# 4channelWormbotShield_fixed_PCBv03_addSS.net
KiCad netlist of a schematic drawn in EAGLE
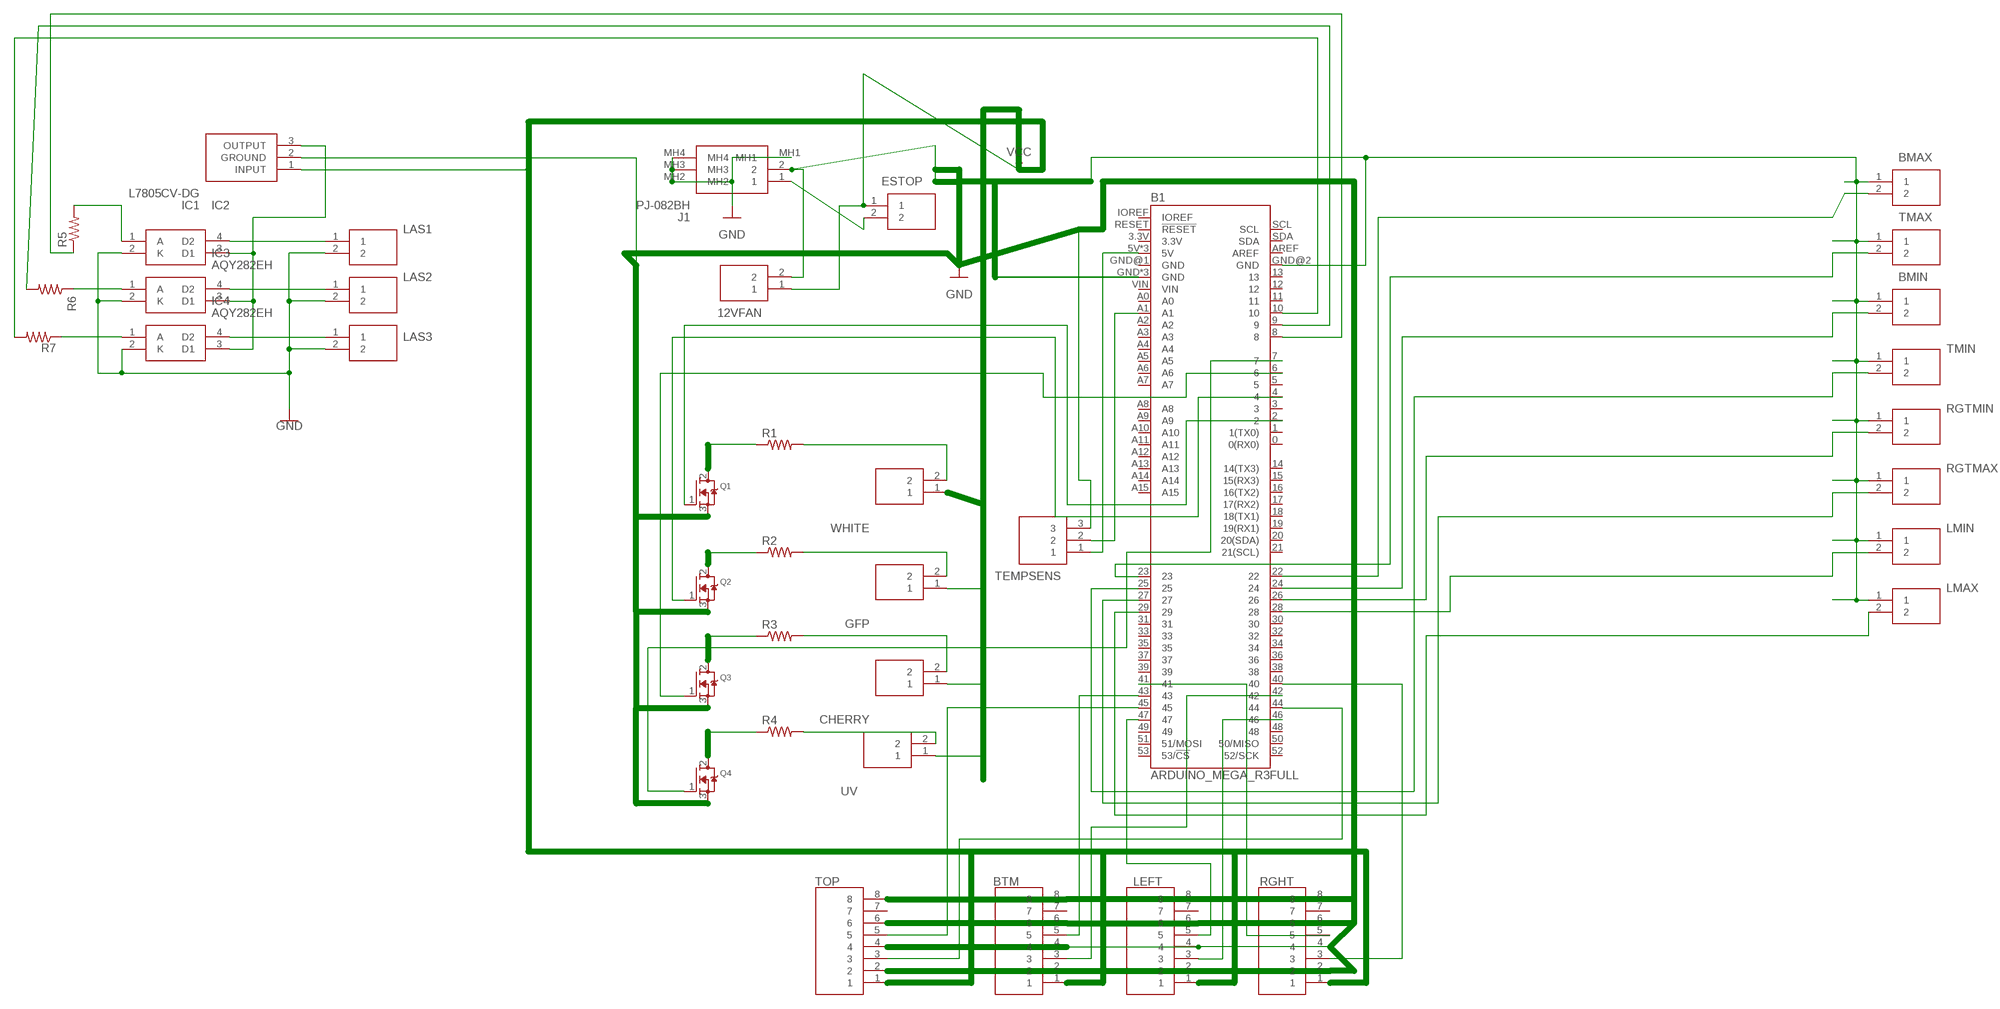
[diagram p0: schematic, sheet 1]

(export (version "E")
  (design (tool "Eeschema 10.0.6"))
  (components
    (comp (ref "12VFAN")
      (value "1725656")
      (footprint "eagle-import:1725656")
      (fields (field (name "MOUSER_PART_NUMBER") "651-1725656"))
      (libsource (lib "eagle-import") (part "1725656"))
    )
    (comp (ref "B1")
      (value "ARDUINO_MEGA_R3FULL")
      (footprint "eagle-import:ARDUINO_MEGA_NO_SILK")
      (libsource (lib "eagle-import") (part "ARDUINO_MEGA_R3FULL"))
    )
    (comp (ref "BMAX")
      (value "1725656")
      (footprint "eagle-import:1725656")
      (fields (field (name "MOUSER_PART_NUMBER") "651-1725656"))
      (libsource (lib "eagle-import") (part "1725656"))
    )
    (comp (ref "BMIN")
      (value "1725656")
      (footprint "eagle-import:1725656")
      (fields (field (name "MOUSER_PART_NUMBER") "651-1725656"))
      (libsource (lib "eagle-import") (part "1725656"))
    )
    (comp (ref "BTM")
      (value "1725711")
      (footprint "eagle-import:1725711")
      (fields (field (name "MOUSER_PART_NUMBER") "651-1725711"))
      (libsource (lib "eagle-import") (part "1725711"))
    )
    (comp (ref "CHERRY")
      (value "1725656")
      (footprint "eagle-import:1725656")
      (fields (field (name "MOUSER_PART_NUMBER") "651-1725656"))
      (libsource (lib "eagle-import") (part "1725656"))
    )
    (comp (ref "ESTOP")
      (value "TB003-500-P02BE")
      (footprint "eagle-import:SHDR2W100P0X500_1X2_1000X780X1")
      (fields (field (name "MOUSER_PART_NUMBER") "490-TB003-500-P02BE"))
      (libsource (lib "eagle-import") (part "TB003-500-P02BE"))
    )
    (comp (ref "GFP")
      (value "1725656")
      (footprint "eagle-import:1725656")
      (fields (field (name "MOUSER_PART_NUMBER") "651-1725656"))
      (libsource (lib "eagle-import") (part "1725656"))
    )
    (comp (ref "IC1")
      (value "L7805CV-DG")
      (footprint "eagle-import:TO255P460X1020X2008-3P")
      (fields (field (name "MOUSER_PART_NUMBER") "511-L7805CV-DG"))
      (libsource (lib "eagle-import") (part "L7805CV-DG"))
    )
    (comp (ref "IC2")
      (value "AQY282EH")
      (footprint "eagle-import:DIP762W57P254L478H340Q4N")
      (fields (field (name "MOUSER_PART_NUMBER") "769-AQY282EH"))
      (libsource (lib "eagle-import") (part "AQY282EH"))
    )
    (comp (ref "IC3")
      (value "AQY282EH")
      (footprint "eagle-import:DIP762W57P254L478H340Q4N")
      (fields (field (name "MOUSER_PART_NUMBER") "769-AQY282EH"))
      (libsource (lib "eagle-import") (part "AQY282EH"))
    )
    (comp (ref "IC4")
      (value "AQY282EH")
      (footprint "eagle-import:DIP762W57P254L478H340Q4N")
      (fields (field (name "MOUSER_PART_NUMBER") "769-AQY282EH"))
      (libsource (lib "eagle-import") (part "AQY282EH"))
    )
    (comp (ref "J1")
      (value "PJ-082BH")
      (footprint "eagle-import:PJ082BH")
      (fields (field (name "MOUSER_PART_NUMBER") "490-PJ-082BH"))
      (libsource (lib "eagle-import") (part "PJ-082BH"))
    )
    (comp (ref "LAS1")
      (value "1725656")
      (footprint "eagle-import:1725656")
      (fields (field (name "MOUSER_PART_NUMBER") "651-1725656"))
      (libsource (lib "eagle-import") (part "1725656"))
    )
    (comp (ref "LAS2")
      (value "1725656")
      (footprint "eagle-import:1725656")
      (fields (field (name "MOUSER_PART_NUMBER") "651-1725656"))
      (libsource (lib "eagle-import") (part "1725656"))
    )
    (comp (ref "LAS3")
      (value "1725656")
      (footprint "eagle-import:1725656")
      (fields (field (name "MOUSER_PART_NUMBER") "651-1725656"))
      (libsource (lib "eagle-import") (part "1725656"))
    )
    (comp (ref "LEFT")
      (value "1725711")
      (footprint "eagle-import:1725711")
      (fields (field (name "MOUSER_PART_NUMBER") "651-1725711"))
      (libsource (lib "eagle-import") (part "1725711"))
    )
    (comp (ref "LMAX")
      (value "1725656")
      (footprint "eagle-import:1725656")
      (fields (field (name "MOUSER_PART_NUMBER") "651-1725656"))
      (libsource (lib "eagle-import") (part "1725656"))
    )
    (comp (ref "LMIN")
      (value "1725656")
      (footprint "eagle-import:1725656")
      (fields (field (name "MOUSER_PART_NUMBER") "651-1725656"))
      (libsource (lib "eagle-import") (part "1725656"))
    )
    (comp (ref "Q1")
      (value "MOSFET-NGDS_TO220V")
      (footprint "eagle-import:TO220V")
      (libsource (lib "eagle-import") (part "MOSFET-NGDS_TO220V"))
    )
    (comp (ref "Q2")
      (value "MOSFET-NGDS_TO220V")
      (footprint "eagle-import:TO220V")
      (libsource (lib "eagle-import") (part "MOSFET-NGDS_TO220V"))
    )
    (comp (ref "Q3")
      (value "MOSFET-NGDS_TO220V")
      (footprint "eagle-import:TO220V")
      (libsource (lib "eagle-import") (part "MOSFET-NGDS_TO220V"))
    )
    (comp (ref "Q4")
      (value "MOSFET-NGDS_TO220V")
      (footprint "eagle-import:TO220V")
      (libsource (lib "eagle-import") (part "MOSFET-NGDS_TO220V"))
    )
    (comp (ref "R1")
      (value "R-US_0207/10")
      (footprint "eagle-import:0207_10")
      (libsource (lib "eagle-import") (part "R-US_0207/10"))
    )
    (comp (ref "R2")
      (value "R-US_0207/10")
      (footprint "eagle-import:0207_10")
      (libsource (lib "eagle-import") (part "R-US_0207/10"))
    )
    (comp (ref "R3")
      (value "R-US_0207/10")
      (footprint "eagle-import:0207_10")
      (libsource (lib "eagle-import") (part "R-US_0207/10"))
    )
    (comp (ref "R4")
      (value "R-US_0207/10")
      (footprint "eagle-import:0207_10")
      (libsource (lib "eagle-import") (part "R-US_0207/10"))
    )
    (comp (ref "R5")
      (value "R-US_0207/10")
      (footprint "eagle-import:0207_10")
      (libsource (lib "eagle-import") (part "R-US_0207/10"))
    )
    (comp (ref "R6")
      (value "R-US_0207/10")
      (footprint "eagle-import:0207_10")
      (libsource (lib "eagle-import") (part "R-US_0207/10"))
    )
    (comp (ref "R7")
      (value "R-US_0207/10")
      (footprint "eagle-import:0207_10")
      (libsource (lib "eagle-import") (part "R-US_0207/10"))
    )
    (comp (ref "RGHT")
      (value "1725711")
      (footprint "eagle-import:1725711")
      (fields (field (name "MOUSER_PART_NUMBER") "651-1725711"))
      (libsource (lib "eagle-import") (part "1725711"))
    )
    (comp (ref "RGTMAX")
      (value "1725656")
      (footprint "eagle-import:1725656")
      (fields (field (name "MOUSER_PART_NUMBER") "651-1725656"))
      (libsource (lib "eagle-import") (part "1725656"))
    )
    (comp (ref "RGTMIN")
      (value "1725656")
      (footprint "eagle-import:1725656")
      (fields (field (name "MOUSER_PART_NUMBER") "651-1725656"))
      (libsource (lib "eagle-import") (part "1725656"))
    )
    (comp (ref "TEMPSENS")
      (value "1725669")
      (footprint "eagle-import:1725669")
      (fields (field (name "MOUSER_PART_NUMBER") "651-1725669"))
      (libsource (lib "eagle-import") (part "1725669"))
    )
    (comp (ref "TMAX")
      (value "1725656")
      (footprint "eagle-import:1725656")
      (fields (field (name "MOUSER_PART_NUMBER") "651-1725656"))
      (libsource (lib "eagle-import") (part "1725656"))
    )
    (comp (ref "TMIN")
      (value "1725656")
      (footprint "eagle-import:1725656")
      (fields (field (name "MOUSER_PART_NUMBER") "651-1725656"))
      (libsource (lib "eagle-import") (part "1725656"))
    )
    (comp (ref "TOP")
      (value "1725711")
      (footprint "eagle-import:1725711")
      (fields (field (name "MOUSER_PART_NUMBER") "651-1725711"))
      (libsource (lib "eagle-import") (part "1725711"))
    )
    (comp (ref "UV")
      (value "1725656")
      (footprint "eagle-import:1725656")
      (fields (field (name "MOUSER_PART_NUMBER") "651-1725656"))
      (libsource (lib "eagle-import") (part "1725656"))
    )
    (comp (ref "WHITE")
      (value "1725656")
      (footprint "eagle-import:1725656")
      (fields (field (name "MOUSER_PART_NUMBER") "651-1725656"))
      (libsource (lib "eagle-import") (part "1725656"))
    )
  )
  (nets
    (net (code "1") (name "GND") (class "Default")
      (node (ref "12VFAN") (pin "2") (pinfunction "2_2") (pintype "bidirectional"))
      (node (ref "B1") (pin "GND") (pinfunction "GND_GND") (pintype "bidirectional"))
      (node (ref "B1") (pin "GND@2") (pinfunction "GND_GND@2") (pintype "bidirectional"))
      (node (ref "B1") (pin "GND@3") (pinfunction "GND_GND@3") (pintype "bidirectional"))
      (node (ref "B1") (pin "GND@4") (pinfunction "GND_GND@4") (pintype "bidirectional"))
      (node (ref "BMAX") (pin "1") (pinfunction "1_1") (pintype "bidirectional"))
      (node (ref "BMIN") (pin "1") (pinfunction "1_1") (pintype "bidirectional"))
      (node (ref "BTM") (pin "2") (pinfunction "2_2") (pintype "bidirectional"))
      (node (ref "BTM") (pin "4") (pinfunction "4_4") (pintype "bidirectional"))
      (node (ref "BTM") (pin "6") (pinfunction "6_6") (pintype "bidirectional"))
      (node (ref "BTM") (pin "8") (pinfunction "8_8") (pintype "bidirectional"))
      (node (ref "IC1") (pin "2") (pinfunction "GROUND_2") (pintype "bidirectional"))
      (node (ref "IC2") (pin "2") (pinfunction "K_2") (pintype "bidirectional"))
      (node (ref "IC3") (pin "2") (pinfunction "K_2") (pintype "bidirectional"))
      (node (ref "IC4") (pin "2") (pinfunction "K_2") (pintype "bidirectional"))
      (node (ref "J1") (pin "2") (pinfunction "2_2") (pintype "bidirectional"))
      (node (ref "J1") (pin "MH1") (pinfunction "MH1_MH1") (pintype "bidirectional"))
      (node (ref "J1") (pin "MH2") (pinfunction "MH2_MH2") (pintype "bidirectional"))
      (node (ref "J1") (pin "MH3") (pinfunction "MH3_MH3") (pintype "bidirectional"))
      (node (ref "J1") (pin "MH4") (pinfunction "MH4_MH4") (pintype "bidirectional"))
      (node (ref "LAS1") (pin "2") (pinfunction "2_2") (pintype "bidirectional"))
      (node (ref "LAS2") (pin "2") (pinfunction "2_2") (pintype "bidirectional"))
      (node (ref "LAS3") (pin "2") (pinfunction "2_2") (pintype "bidirectional"))
      (node (ref "LEFT") (pin "2") (pinfunction "2_2") (pintype "bidirectional"))
      (node (ref "LEFT") (pin "4") (pinfunction "4_4") (pintype "bidirectional"))
      (node (ref "LEFT") (pin "6") (pinfunction "6_6") (pintype "bidirectional"))
      (node (ref "LEFT") (pin "8") (pinfunction "8_8") (pintype "bidirectional"))
      (node (ref "LMAX") (pin "1") (pinfunction "1_1") (pintype "bidirectional"))
      (node (ref "LMIN") (pin "1") (pinfunction "1_1") (pintype "bidirectional"))
      (node (ref "Q1") (pin "3") (pinfunction "S_3") (pintype "bidirectional"))
      (node (ref "Q2") (pin "3") (pinfunction "S_3") (pintype "bidirectional"))
      (node (ref "Q3") (pin "3") (pinfunction "S_3") (pintype "bidirectional"))
      (node (ref "Q4") (pin "3") (pinfunction "S_3") (pintype "bidirectional"))
      (node (ref "RGHT") (pin "2") (pinfunction "2_2") (pintype "bidirectional"))
      (node (ref "RGHT") (pin "4") (pinfunction "4_4") (pintype "bidirectional"))
      (node (ref "RGHT") (pin "6") (pinfunction "6_6") (pintype "bidirectional"))
      (node (ref "RGHT") (pin "8") (pinfunction "8_8") (pintype "bidirectional"))
      (node (ref "RGTMAX") (pin "1") (pinfunction "1_1") (pintype "bidirectional"))
      (node (ref "RGTMIN") (pin "1") (pinfunction "1_1") (pintype "bidirectional"))
      (node (ref "TEMPSENS") (pin "3") (pinfunction "3_3") (pintype "bidirectional"))
      (node (ref "TMAX") (pin "1") (pinfunction "1_1") (pintype "bidirectional"))
      (node (ref "TMIN") (pin "1") (pinfunction "1_1") (pintype "bidirectional"))
      (node (ref "TOP") (pin "2") (pinfunction "2_2") (pintype "bidirectional"))
      (node (ref "TOP") (pin "4") (pinfunction "4_4") (pintype "bidirectional"))
      (node (ref "TOP") (pin "6") (pinfunction "6_6") (pintype "bidirectional"))
      (node (ref "TOP") (pin "8") (pinfunction "8_8") (pintype "bidirectional"))
    )
    (net (code "2") (name "Net-(B1-5V-Pad5V@1)") (class "Default")
      (node (ref "B1") (pin "5V") (pinfunction "5V_5V") (pintype "bidirectional"))
      (node (ref "B1") (pin "5V@1") (pinfunction "5V_5V@1") (pintype "bidirectional"))
      (node (ref "B1") (pin "5V@2") (pinfunction "5V_5V@2") (pintype "bidirectional"))
      (node (ref "TEMPSENS") (pin "1") (pinfunction "1_1") (pintype "bidirectional"))
    )
    (net (code "3") (name "Net-(B1-Pad8)") (class "Default")
      (node (ref "B1") (pin "8") (pinfunction "8_8") (pintype "bidirectional"))
      (node (ref "R5") (pin "1") (pinfunction "1_1") (pintype "passive"))
    )
    (net (code "4") (name "Net-(B1-Pad9)") (class "Default")
      (node (ref "B1") (pin "9") (pinfunction "9_9") (pintype "bidirectional"))
      (node (ref "R6") (pin "2") (pinfunction "2_2") (pintype "passive"))
    )
    (net (code "5") (name "Net-(B1-Pad10)") (class "Default")
      (node (ref "B1") (pin "10") (pinfunction "10_10") (pintype "bidirectional"))
      (node (ref "R7") (pin "2") (pinfunction "2_2") (pintype "passive"))
    )
    (net (code "6") (name "Net-(B1-Pad22)") (class "Default")
      (node (ref "B1") (pin "22") (pinfunction "22_22") (pintype "bidirectional"))
      (node (ref "BMAX") (pin "2") (pinfunction "2_2") (pintype "bidirectional"))
    )
    (net (code "7") (name "Net-(B1-Pad23)") (class "Default")
      (node (ref "B1") (pin "23") (pinfunction "23_23") (pintype "bidirectional"))
      (node (ref "TMAX") (pin "2") (pinfunction "2_2") (pintype "bidirectional"))
    )
    (net (code "8") (name "Net-(B1-Pad24)") (class "Default")
      (node (ref "B1") (pin "24") (pinfunction "24_24") (pintype "bidirectional"))
      (node (ref "BMIN") (pin "2") (pinfunction "2_2") (pintype "bidirectional"))
    )
    (net (code "9") (name "Net-(B1-Pad25)") (class "Default")
      (node (ref "B1") (pin "25") (pinfunction "25_25") (pintype "bidirectional"))
      (node (ref "TMIN") (pin "2") (pinfunction "2_2") (pintype "bidirectional"))
    )
    (net (code "10") (name "Net-(B1-Pad26)") (class "Default")
      (node (ref "B1") (pin "26") (pinfunction "26_26") (pintype "bidirectional"))
      (node (ref "RGTMIN") (pin "2") (pinfunction "2_2") (pintype "bidirectional"))
    )
    (net (code "11") (name "Net-(B1-Pad27)") (class "Default")
      (node (ref "B1") (pin "27") (pinfunction "27_27") (pintype "bidirectional"))
      (node (ref "RGTMAX") (pin "2") (pinfunction "2_2") (pintype "bidirectional"))
    )
    (net (code "12") (name "Net-(B1-Pad28)") (class "Default")
      (node (ref "B1") (pin "28") (pinfunction "28_28") (pintype "bidirectional"))
      (node (ref "LMIN") (pin "2") (pinfunction "2_2") (pintype "bidirectional"))
    )
    (net (code "13") (name "Net-(B1-Pad29)") (class "Default")
      (node (ref "B1") (pin "29") (pinfunction "29_29") (pintype "bidirectional"))
      (node (ref "LMAX") (pin "2") (pinfunction "2_2") (pintype "bidirectional"))
    )
    (net (code "14") (name "Net-(B1-Pad40)") (class "Default")
      (node (ref "B1") (pin "40") (pinfunction "40_40") (pintype "bidirectional"))
      (node (ref "RGHT") (pin "3") (pinfunction "3_3") (pintype "bidirectional"))
    )
    (net (code "15") (name "Net-(B1-Pad41)") (class "Default")
      (node (ref "B1") (pin "41") (pinfunction "41_41") (pintype "bidirectional"))
      (node (ref "RGHT") (pin "5") (pinfunction "5_5") (pintype "bidirectional"))
    )
    (net (code "16") (name "Net-(B1-Pad42)") (class "Default")
      (node (ref "B1") (pin "42") (pinfunction "42_42") (pintype "bidirectional"))
      (node (ref "BTM") (pin "3") (pinfunction "3_3") (pintype "bidirectional"))
    )
    (net (code "17") (name "Net-(B1-Pad43)") (class "Default")
      (node (ref "B1") (pin "43") (pinfunction "43_43") (pintype "bidirectional"))
      (node (ref "BTM") (pin "5") (pinfunction "5_5") (pintype "bidirectional"))
    )
    (net (code "18") (name "Net-(B1-Pad44)") (class "Default")
      (node (ref "B1") (pin "44") (pinfunction "44_44") (pintype "bidirectional"))
      (node (ref "TOP") (pin "3") (pinfunction "3_3") (pintype "bidirectional"))
    )
    (net (code "19") (name "Net-(B1-Pad45)") (class "Default")
      (node (ref "B1") (pin "45") (pinfunction "45_45") (pintype "bidirectional"))
      (node (ref "TOP") (pin "5") (pinfunction "5_5") (pintype "bidirectional"))
    )
    (net (code "20") (name "Net-(B1-Pad46)") (class "Default")
      (node (ref "B1") (pin "46") (pinfunction "46_46") (pintype "bidirectional"))
      (node (ref "LEFT") (pin "3") (pinfunction "3_3") (pintype "bidirectional"))
    )
    (net (code "21") (name "Net-(B1-Pad47)") (class "Default")
      (node (ref "B1") (pin "47") (pinfunction "47_47") (pintype "bidirectional"))
      (node (ref "LEFT") (pin "5") (pinfunction "5_5") (pintype "bidirectional"))
    )
    (net (code "22") (name "Net-(B1-PadA1)") (class "Default")
      (node (ref "B1") (pin "A1") (pinfunction "A1_A1") (pintype "bidirectional"))
      (node (ref "TEMPSENS") (pin "2") (pinfunction "2_2") (pintype "bidirectional"))
    )
    (net (code "23") (name "Net-(CHERRY-Pad2)") (class "Default")
      (node (ref "CHERRY") (pin "2") (pinfunction "2_2") (pintype "bidirectional"))
      (node (ref "R3") (pin "2") (pinfunction "2_2") (pintype "passive"))
    )
    (net (code "24") (name "Net-(ESTOP-Pad2)") (class "Default")
      (node (ref "ESTOP") (pin "2") (pinfunction "2_2") (pintype "bidirectional"))
      (node (ref "J1") (pin "1") (pinfunction "1_1") (pintype "bidirectional"))
    )
    (net (code "25") (name "Net-(GFP-Pad2)") (class "Default")
      (node (ref "GFP") (pin "2") (pinfunction "2_2") (pintype "bidirectional"))
      (node (ref "R2") (pin "2") (pinfunction "2_2") (pintype "passive"))
    )
    (net (code "26") (name "Net-(IC1-OUTPUT)") (class "Default")
      (node (ref "IC1") (pin "3") (pinfunction "OUTPUT_3") (pintype "bidirectional"))
      (node (ref "IC2") (pin "3") (pinfunction "D1_3") (pintype "bidirectional"))
      (node (ref "IC3") (pin "3") (pinfunction "D1_3") (pintype "bidirectional"))
      (node (ref "IC4") (pin "3") (pinfunction "D1_3") (pintype "bidirectional"))
    )
    (net (code "27") (name "Net-(IC2-A)") (class "Default")
      (node (ref "IC2") (pin "1") (pinfunction "A_1") (pintype "bidirectional"))
      (node (ref "R5") (pin "2") (pinfunction "2_2") (pintype "passive"))
    )
    (net (code "28") (name "Net-(IC2-D2)") (class "Default")
      (node (ref "IC2") (pin "4") (pinfunction "D2_4") (pintype "bidirectional"))
      (node (ref "LAS1") (pin "1") (pinfunction "1_1") (pintype "bidirectional"))
    )
    (net (code "29") (name "Net-(IC3-A)") (class "Default")
      (node (ref "IC3") (pin "1") (pinfunction "A_1") (pintype "bidirectional"))
      (node (ref "R6") (pin "1") (pinfunction "1_1") (pintype "passive"))
    )
    (net (code "30") (name "Net-(IC3-D2)") (class "Default")
      (node (ref "IC3") (pin "4") (pinfunction "D2_4") (pintype "bidirectional"))
      (node (ref "LAS2") (pin "1") (pinfunction "1_1") (pintype "bidirectional"))
    )
    (net (code "31") (name "Net-(IC4-A)") (class "Default")
      (node (ref "IC4") (pin "1") (pinfunction "A_1") (pintype "bidirectional"))
      (node (ref "R7") (pin "1") (pinfunction "1_1") (pintype "passive"))
    )
    (net (code "32") (name "Net-(IC4-D2)") (class "Default")
      (node (ref "IC4") (pin "4") (pinfunction "D2_4") (pintype "bidirectional"))
      (node (ref "LAS3") (pin "1") (pinfunction "1_1") (pintype "bidirectional"))
    )
    (net (code "33") (name "Net-(Q1-D)") (class "Default")
      (node (ref "Q1") (pin "2") (pinfunction "D_2") (pintype "bidirectional"))
      (node (ref "R1") (pin "1") (pinfunction "1_1") (pintype "passive"))
    )
    (net (code "34") (name "Net-(Q1-G)") (class "Default")
      (node (ref "B1") (pin "2") (pinfunction "2_2") (pintype "bidirectional"))
      (node (ref "Q1") (pin "1") (pinfunction "G_1") (pintype "bidirectional"))
    )
    (net (code "35") (name "Net-(Q2-D)") (class "Default")
      (node (ref "Q2") (pin "2") (pinfunction "D_2") (pintype "bidirectional"))
      (node (ref "R2") (pin "1") (pinfunction "1_1") (pintype "passive"))
    )
    (net (code "36") (name "Net-(Q2-G)") (class "Default")
      (node (ref "B1") (pin "4") (pinfunction "4_4") (pintype "bidirectional"))
      (node (ref "Q2") (pin "1") (pinfunction "G_1") (pintype "bidirectional"))
    )
    (net (code "37") (name "Net-(Q3-D)") (class "Default")
      (node (ref "Q3") (pin "2") (pinfunction "D_2") (pintype "bidirectional"))
      (node (ref "R3") (pin "1") (pinfunction "1_1") (pintype "passive"))
    )
    (net (code "38") (name "Net-(Q3-G)") (class "Default")
      (node (ref "B1") (pin "6") (pinfunction "6_6") (pintype "bidirectional"))
      (node (ref "Q3") (pin "1") (pinfunction "G_1") (pintype "bidirectional"))
    )
    (net (code "39") (name "Net-(Q4-D)") (class "Default")
      (node (ref "Q4") (pin "2") (pinfunction "D_2") (pintype "bidirectional"))
      (node (ref "R4") (pin "1") (pinfunction "1_1") (pintype "passive"))
    )
    (net (code "40") (name "Net-(Q4-G)") (class "Default")
      (node (ref "B1") (pin "7") (pinfunction "7_7") (pintype "bidirectional"))
      (node (ref "Q4") (pin "1") (pinfunction "G_1") (pintype "bidirectional"))
    )
    (net (code "41") (name "Net-(R1-Pad2)") (class "Default")
      (node (ref "R1") (pin "2") (pinfunction "2_2") (pintype "passive"))
      (node (ref "WHITE") (pin "2") (pinfunction "2_2") (pintype "bidirectional"))
    )
    (net (code "42") (name "Net-(R4-Pad2)") (class "Default")
      (node (ref "R4") (pin "2") (pinfunction "2_2") (pintype "passive"))
      (node (ref "UV") (pin "2") (pinfunction "2_2") (pintype "bidirectional"))
    )
    (net (code "43") (name "VCC") (class "Default")
      (node (ref "12VFAN") (pin "1") (pinfunction "1_1") (pintype "bidirectional"))
      (node (ref "BTM") (pin "1") (pinfunction "1_1") (pintype "bidirectional"))
      (node (ref "CHERRY") (pin "1") (pinfunction "1_1") (pintype "bidirectional"))
      (node (ref "ESTOP") (pin "1") (pinfunction "1_1") (pintype "bidirectional"))
      (node (ref "GFP") (pin "1") (pinfunction "1_1") (pintype "bidirectional"))
      (node (ref "IC1") (pin "1") (pinfunction "INPUT_1") (pintype "bidirectional"))
      (node (ref "LEFT") (pin "1") (pinfunction "1_1") (pintype "bidirectional"))
      (node (ref "RGHT") (pin "1") (pinfunction "1_1") (pintype "bidirectional"))
      (node (ref "TOP") (pin "1") (pinfunction "1_1") (pintype "bidirectional"))
      (node (ref "UV") (pin "1") (pinfunction "1_1") (pintype "bidirectional"))
      (node (ref "WHITE") (pin "1") (pinfunction "1_1") (pintype "bidirectional"))
    )
    (net (code "44") (name "unconnected-(B1-0(RX0)-Pad0)") (class "Default")
      (node (ref "B1") (pin "0") (pinfunction "0(RX0)_0") (pintype "bidirectional"))
    )
    (net (code "45") (name "unconnected-(B1-1(TX0)-Pad1)") (class "Default")
      (node (ref "B1") (pin "1") (pinfunction "1(TX0)_1") (pintype "bidirectional"))
    )
    (net (code "46") (name "unconnected-(B1-14(TX3)-Pad14)") (class "Default")
      (node (ref "B1") (pin "14") (pinfunction "14(TX3)_14") (pintype "bidirectional"))
    )
    (net (code "47") (name "unconnected-(B1-15(RX3)-Pad15)") (class "Default")
      (node (ref "B1") (pin "15") (pinfunction "15(RX3)_15") (pintype "bidirectional"))
    )
    (net (code "48") (name "unconnected-(B1-16(TX2)-Pad16)") (class "Default")
      (node (ref "B1") (pin "16") (pinfunction "16(TX2)_16") (pintype "bidirectional"))
    )
    (net (code "49") (name "unconnected-(B1-17(RX2)-Pad17)") (class "Default")
      (node (ref "B1") (pin "17") (pinfunction "17(RX2)_17") (pintype "bidirectional"))
    )
    (net (code "50") (name "unconnected-(B1-18(TX1)-Pad18)") (class "Default")
      (node (ref "B1") (pin "18") (pinfunction "18(TX1)_18") (pintype "bidirectional"))
    )
    (net (code "51") (name "unconnected-(B1-19(RX1)-Pad19)") (class "Default")
      (node (ref "B1") (pin "19") (pinfunction "19(RX1)_19") (pintype "bidirectional"))
    )
    (net (code "52") (name "unconnected-(B1-20(SDA)-Pad20)") (class "Default")
      (node (ref "B1") (pin "20") (pinfunction "20(SDA)_20") (pintype "bidirectional"))
    )
    (net (code "53") (name "unconnected-(B1-21(SCL)-Pad21)") (class "Default")
      (node (ref "B1") (pin "21") (pinfunction "21(SCL)_21") (pintype "bidirectional"))
    )
    (net (code "54") (name "unconnected-(B1-50{slash}MISO-Pad50)") (class "Default")
      (node (ref "B1") (pin "50") (pinfunction "50/MISO_50") (pintype "bidirectional"))
    )
    (net (code "55") (name "unconnected-(B1-51{slash}MOSI-Pad51)") (class "Default")
      (node (ref "B1") (pin "51") (pinfunction "51/MOSI_51") (pintype "bidirectional"))
    )
    (net (code "56") (name "unconnected-(B1-52{slash}SCK-Pad52)") (class "Default")
      (node (ref "B1") (pin "52") (pinfunction "52/SCK_52") (pintype "bidirectional"))
    )
    (net (code "57") (name "unconnected-(B1-53{slash}~{CS}-Pad53)") (class "Default")
      (node (ref "B1") (pin "53") (pinfunction "53/~{CS}_53") (pintype "bidirectional"))
    )
    (net (code "58") (name "unconnected-(B1-GND-PadGND@1)") (class "Default")
      (node (ref "B1") (pin "GND@1") (pinfunction "GND_GND@1") (pintype "bidirectional"))
    )
    (net (code "59") (name "unconnected-(B1-Pad3)") (class "Default")
      (node (ref "B1") (pin "3") (pinfunction "3_3") (pintype "bidirectional"))
    )
    (net (code "60") (name "unconnected-(B1-Pad3.3V)") (class "Default")
      (node (ref "B1") (pin "3.3V") (pinfunction "3.3V_3.3V") (pintype "bidirectional"))
    )
    (net (code "61") (name "unconnected-(B1-Pad5)") (class "Default")
      (node (ref "B1") (pin "5") (pinfunction "5_5") (pintype "bidirectional"))
    )
    (net (code "62") (name "unconnected-(B1-Pad11)") (class "Default")
      (node (ref "B1") (pin "11") (pinfunction "11_11") (pintype "bidirectional"))
    )
    (net (code "63") (name "unconnected-(B1-Pad12)") (class "Default")
      (node (ref "B1") (pin "12") (pinfunction "12_12") (pintype "bidirectional"))
    )
    (net (code "64") (name "unconnected-(B1-Pad13)") (class "Default")
      (node (ref "B1") (pin "13") (pinfunction "13_13") (pintype "bidirectional"))
    )
    (net (code "65") (name "unconnected-(B1-Pad30)") (class "Default")
      (node (ref "B1") (pin "30") (pinfunction "30_30") (pintype "bidirectional"))
    )
    (net (code "66") (name "unconnected-(B1-Pad31)") (class "Default")
      (node (ref "B1") (pin "31") (pinfunction "31_31") (pintype "bidirectional"))
    )
    (net (code "67") (name "unconnected-(B1-Pad32)") (class "Default")
      (node (ref "B1") (pin "32") (pinfunction "32_32") (pintype "bidirectional"))
    )
    (net (code "68") (name "unconnected-(B1-Pad33)") (class "Default")
      (node (ref "B1") (pin "33") (pinfunction "33_33") (pintype "bidirectional"))
    )
    (net (code "69") (name "unconnected-(B1-Pad34)") (class "Default")
      (node (ref "B1") (pin "34") (pinfunction "34_34") (pintype "bidirectional"))
    )
    (net (code "70") (name "unconnected-(B1-Pad35)") (class "Default")
      (node (ref "B1") (pin "35") (pinfunction "35_35") (pintype "bidirectional"))
    )
    (net (code "71") (name "unconnected-(B1-Pad36)") (class "Default")
      (node (ref "B1") (pin "36") (pinfunction "36_36") (pintype "bidirectional"))
    )
    (net (code "72") (name "unconnected-(B1-Pad37)") (class "Default")
      (node (ref "B1") (pin "37") (pinfunction "37_37") (pintype "bidirectional"))
    )
    (net (code "73") (name "unconnected-(B1-Pad38)") (class "Default")
      (node (ref "B1") (pin "38") (pinfunction "38_38") (pintype "bidirectional"))
    )
    (net (code "74") (name "unconnected-(B1-Pad39)") (class "Default")
      (node (ref "B1") (pin "39") (pinfunction "39_39") (pintype "bidirectional"))
    )
    (net (code "75") (name "unconnected-(B1-Pad48)") (class "Default")
      (node (ref "B1") (pin "48") (pinfunction "48_48") (pintype "bidirectional"))
    )
    (net (code "76") (name "unconnected-(B1-Pad49)") (class "Default")
      (node (ref "B1") (pin "49") (pinfunction "49_49") (pintype "bidirectional"))
    )
    (net (code "77") (name "unconnected-(B1-PadA0)") (class "Default")
      (node (ref "B1") (pin "A0") (pinfunction "A0_A0") (pintype "bidirectional"))
    )
    (net (code "78") (name "unconnected-(B1-PadA2)") (class "Default")
      (node (ref "B1") (pin "A2") (pinfunction "A2_A2") (pintype "bidirectional"))
    )
    (net (code "79") (name "unconnected-(B1-PadA3)") (class "Default")
      (node (ref "B1") (pin "A3") (pinfunction "A3_A3") (pintype "bidirectional"))
    )
    (net (code "80") (name "unconnected-(B1-PadA4)") (class "Default")
      (node (ref "B1") (pin "A4") (pinfunction "A4_A4") (pintype "bidirectional"))
    )
    (net (code "81") (name "unconnected-(B1-PadA5)") (class "Default")
      (node (ref "B1") (pin "A5") (pinfunction "A5_A5") (pintype "bidirectional"))
    )
    (net (code "82") (name "unconnected-(B1-PadA6)") (class "Default")
      (node (ref "B1") (pin "A6") (pinfunction "A6_A6") (pintype "bidirectional"))
    )
    (net (code "83") (name "unconnected-(B1-PadA7)") (class "Default")
      (node (ref "B1") (pin "A7") (pinfunction "A7_A7") (pintype "bidirectional"))
    )
    (net (code "84") (name "unconnected-(B1-PadA8)") (class "Default")
      (node (ref "B1") (pin "A8") (pinfunction "A8_A8") (pintype "bidirectional"))
    )
    (net (code "85") (name "unconnected-(B1-PadA9)") (class "Default")
      (node (ref "B1") (pin "A9") (pinfunction "A9_A9") (pintype "bidirectional"))
    )
    (net (code "86") (name "unconnected-(B1-PadA10)") (class "Default")
      (node (ref "B1") (pin "A10") (pinfunction "A10_A10") (pintype "bidirectional"))
    )
    (net (code "87") (name "unconnected-(B1-PadA11)") (class "Default")
      (node (ref "B1") (pin "A11") (pinfunction "A11_A11") (pintype "bidirectional"))
    )
    (net (code "88") (name "unconnected-(B1-PadA12)") (class "Default")
      (node (ref "B1") (pin "A12") (pinfunction "A12_A12") (pintype "bidirectional"))
    )
    (net (code "89") (name "unconnected-(B1-PadA13)") (class "Default")
      (node (ref "B1") (pin "A13") (pinfunction "A13_A13") (pintype "bidirectional"))
    )
    (net (code "90") (name "unconnected-(B1-PadA14)") (class "Default")
      (node (ref "B1") (pin "A14") (pinfunction "A14_A14") (pintype "bidirectional"))
    )
    (net (code "91") (name "unconnected-(B1-PadA15)") (class "Default")
      (node (ref "B1") (pin "A15") (pinfunction "A15_A15") (pintype "bidirectional"))
    )
    (net (code "92") (name "unconnected-(B1-PadAREF)") (class "Default")
      (node (ref "B1") (pin "AREF") (pinfunction "AREF_AREF") (pintype "bidirectional"))
    )
    (net (code "93") (name "unconnected-(B1-PadIOREF)") (class "Default")
      (node (ref "B1") (pin "IOREF") (pinfunction "IOREF_IOREF") (pintype "bidirectional"))
    )
    (net (code "94") (name "unconnected-(B1-PadSCL)") (class "Default")
      (node (ref "B1") (pin "SCL") (pinfunction "SCL_SCL") (pintype "bidirectional"))
    )
    (net (code "95") (name "unconnected-(B1-PadSDA)") (class "Default")
      (node (ref "B1") (pin "SDA") (pinfunction "SDA_SDA") (pintype "bidirectional"))
    )
    (net (code "96") (name "unconnected-(B1-PadVIN)") (class "Default")
      (node (ref "B1") (pin "VIN") (pinfunction "VIN_VIN") (pintype "bidirectional"))
    )
    (net (code "97") (name "unconnected-(B1-~{RESET}-PadRESET)") (class "Default")
      (node (ref "B1") (pin "RESET") (pinfunction "~{RESET}_RESET") (pintype "bidirectional"))
    )
    (net (code "98") (name "unconnected-(BTM-Pad7)") (class "Default")
      (node (ref "BTM") (pin "7") (pinfunction "7_7") (pintype "bidirectional"))
    )
    (net (code "99") (name "unconnected-(LEFT-Pad7)") (class "Default")
      (node (ref "LEFT") (pin "7") (pinfunction "7_7") (pintype "bidirectional"))
    )
    (net (code "100") (name "unconnected-(RGHT-Pad7)") (class "Default")
      (node (ref "RGHT") (pin "7") (pinfunction "7_7") (pintype "bidirectional"))
    )
    (net (code "101") (name "unconnected-(TOP-Pad7)") (class "Default")
      (node (ref "TOP") (pin "7") (pinfunction "7_7") (pintype "bidirectional"))
    )
  )
)
